# smartcar_shield.net
KiCad netlist of a schematic drawn in EAGLE
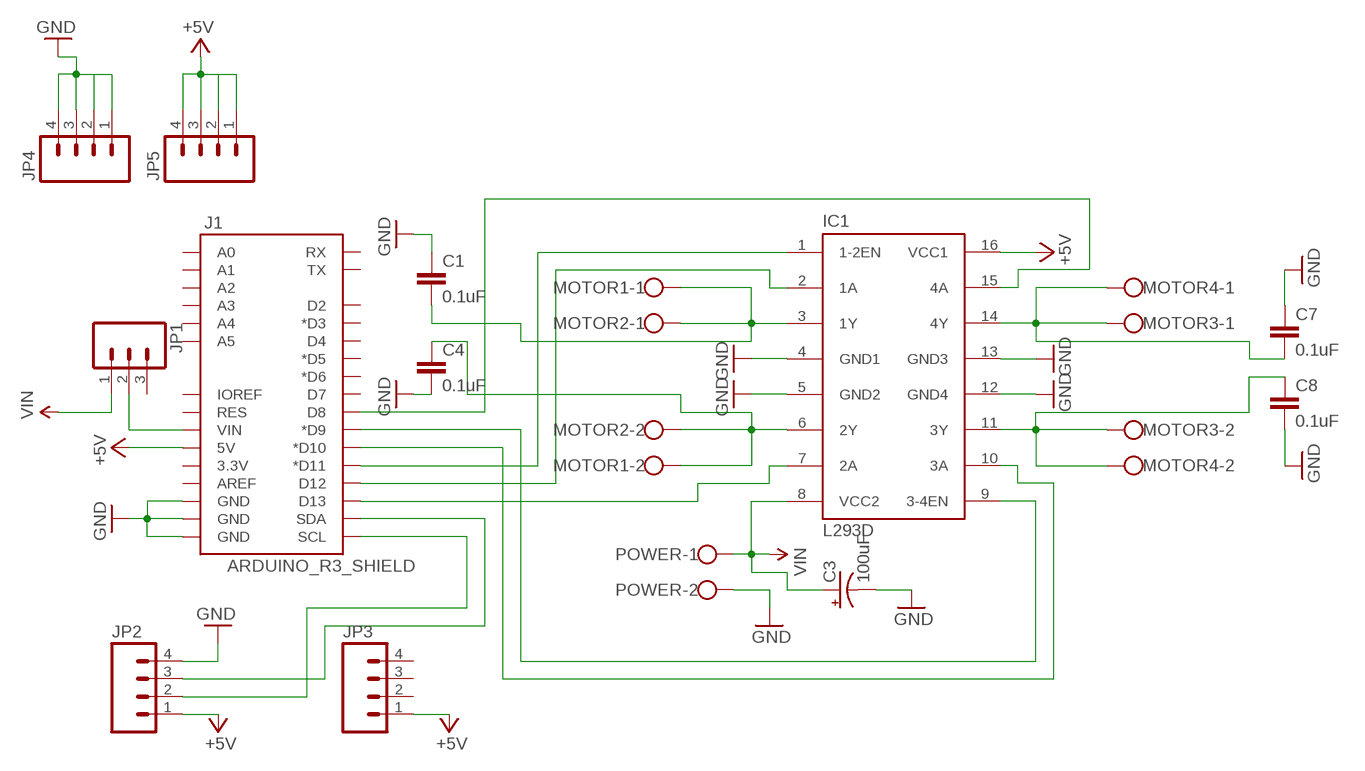
[diagram p0: schematic, sheet 1]

(export (version "E")
  (design (tool "Eeschema 10.0.6"))
  (components
    (comp (ref "C1")
      (value "0.1uF")
      (footprint "eagle-import:CAP-PTH-SMALL-KIT")
      (libsource (lib "eagle-import") (part "CAPKIT"))
    )
    (comp (ref "C3")
      (value "100uF")
      (footprint "eagle-import:CPOL-RADIAL-10UF-25V")
      (libsource (lib "eagle-import") (part "CAP_POLPTH2"))
    )
    (comp (ref "C4")
      (value "0.1uF")
      (footprint "eagle-import:CAP-PTH-SMALL-KIT")
      (libsource (lib "eagle-import") (part "CAPKIT"))
    )
    (comp (ref "C7")
      (value "0.1uF")
      (footprint "eagle-import:CAP-PTH-SMALL-KIT")
      (libsource (lib "eagle-import") (part "CAPKIT"))
    )
    (comp (ref "C8")
      (value "0.1uF")
      (footprint "eagle-import:CAP-PTH-SMALL-KIT")
      (libsource (lib "eagle-import") (part "CAPKIT"))
    )
    (comp (ref "IC1")
      (value "L293D")
      (footprint "eagle-import:DIL16")
      (libsource (lib "eagle-import") (part "L293D"))
    )
    (comp (ref "J1")
      (value "ARDUINO_R3_SHIELD")
      (footprint "eagle-import:UNO_R3_SHIELD")
      (libsource (lib "eagle-import") (part "ARDUINO_R3_SHIELD"))
    )
    (comp (ref "JP1")
      (value "M03PTH")
      (footprint "eagle-import:1X03")
      (libsource (lib "eagle-import") (part "M03PTH"))
    )
    (comp (ref "JP2")
      (value "M04NO_SILK_ALL_ROUND")
      (footprint "eagle-import:1X04_NO_SILK_ALL_ROUND")
      (libsource (lib "eagle-import") (part "M04NO_SILK_ALL_ROUND"))
    )
    (comp (ref "JP3")
      (value "M04NO_SILK_ALL_ROUND")
      (footprint "eagle-import:1X04_NO_SILK_ALL_ROUND")
      (libsource (lib "eagle-import") (part "M04NO_SILK_ALL_ROUND"))
    )
    (comp (ref "JP4")
      (value "M04NO_SILK_ALL_ROUND")
      (footprint "eagle-import:1X04_NO_SILK_ALL_ROUND")
      (libsource (lib "eagle-import") (part "M04NO_SILK_ALL_ROUND"))
    )
    (comp (ref "JP5")
      (value "M04NO_SILK_ALL_ROUND")
      (footprint "eagle-import:1X04_NO_SILK_ALL_ROUND")
      (libsource (lib "eagle-import") (part "M04NO_SILK_ALL_ROUND"))
    )
    (comp (ref "MOTOR1")
      (value "W237-102")
      (footprint "eagle-import:W237-102")
      (fields (field (name "MPN") "237-102"))
      (libsource (lib "eagle-import") (part "W237-102"))
    )
    (comp (ref "MOTOR2")
      (value "W237-102")
      (footprint "eagle-import:W237-102")
      (fields (field (name "MPN") "237-102"))
      (libsource (lib "eagle-import") (part "W237-102"))
    )
    (comp (ref "MOTOR3")
      (value "W237-102")
      (footprint "eagle-import:W237-102")
      (fields (field (name "MPN") "237-102"))
      (libsource (lib "eagle-import") (part "W237-102"))
    )
    (comp (ref "MOTOR4")
      (value "W237-102")
      (footprint "eagle-import:W237-102")
      (fields (field (name "MPN") "237-102"))
      (libsource (lib "eagle-import") (part "W237-102"))
    )
    (comp (ref "POWER")
      (value "W237-102")
      (footprint "eagle-import:W237-102")
      (fields (field (name "MPN") "237-102"))
      (libsource (lib "eagle-import") (part "W237-102"))
    )
  )
  (nets
    (net (code "1") (name "+5V") (class "Default")
      (node (ref "IC1") (pin "16") (pinfunction "VCC1_16") (pintype "power_in"))
      (node (ref "J1") (pin "5V") (pinfunction "5V_5V") (pintype "bidirectional"))
      (node (ref "JP2") (pin "1") (pinfunction "1_1") (pintype "passive"))
      (node (ref "JP3") (pin "1") (pinfunction "1_1") (pintype "passive"))
      (node (ref "JP5") (pin "1") (pinfunction "1_1") (pintype "passive"))
      (node (ref "JP5") (pin "2") (pinfunction "2_2") (pintype "passive"))
      (node (ref "JP5") (pin "3") (pinfunction "3_3") (pintype "passive"))
      (node (ref "JP5") (pin "4") (pinfunction "4_4") (pintype "passive"))
    )
    (net (code "2") (name "12V") (class "Default")
      (node (ref "C3") (pin "1") (pinfunction "+_1") (pintype "passive"))
      (node (ref "IC1") (pin "8") (pinfunction "VCC2_8") (pintype "power_in"))
      (node (ref "JP1") (pin "1") (pinfunction "1_1") (pintype "passive"))
      (node (ref "POWER") (pin "1") (pinfunction "KL_1") (pintype "passive"))
    )
    (net (code "3") (name "GND") (class "Default")
      (node (ref "C1") (pin "1") (pinfunction "1_1") (pintype "passive"))
      (node (ref "C3") (pin "2") (pinfunction "-_2") (pintype "passive"))
      (node (ref "C4") (pin "2") (pinfunction "2_2") (pintype "passive"))
      (node (ref "C7") (pin "1") (pinfunction "1_1") (pintype "passive"))
      (node (ref "C8") (pin "2") (pinfunction "2_2") (pintype "passive"))
      (node (ref "IC1") (pin "12") (pinfunction "GND4_12") (pintype "power_in"))
      (node (ref "IC1") (pin "13") (pinfunction "GND3_13") (pintype "power_in"))
      (node (ref "IC1") (pin "4") (pinfunction "GND1_4") (pintype "power_in"))
      (node (ref "IC1") (pin "5") (pinfunction "GND2_5") (pintype "power_in"))
      (node (ref "J1") (pin "GND@0") (pinfunction "GND_GND@0") (pintype "bidirectional"))
      (node (ref "J1") (pin "GND@1") (pinfunction "GND_GND@1") (pintype "bidirectional"))
      (node (ref "J1") (pin "GND@2") (pinfunction "GND_GND@2") (pintype "bidirectional"))
      (node (ref "JP2") (pin "4") (pinfunction "4_4") (pintype "passive"))
      (node (ref "JP4") (pin "1") (pinfunction "1_1") (pintype "passive"))
      (node (ref "JP4") (pin "2") (pinfunction "2_2") (pintype "passive"))
      (node (ref "JP4") (pin "3") (pinfunction "3_3") (pintype "passive"))
      (node (ref "JP4") (pin "4") (pinfunction "4_4") (pintype "passive"))
      (node (ref "POWER") (pin "2") (pinfunction "KL_2") (pintype "passive"))
    )
    (net (code "4") (name "Net-(IC1-1-2EN)") (class "Default")
      (node (ref "IC1") (pin "1") (pinfunction "1-2EN_1") (pintype "input"))
      (node (ref "J1") (pin "D11") (pinfunction "*D11_D11") (pintype "bidirectional"))
    )
    (net (code "5") (name "Net-(IC1-1A)") (class "Default")
      (node (ref "IC1") (pin "2") (pinfunction "1A_2") (pintype "input"))
      (node (ref "J1") (pin "D12") (pinfunction "D12_D12") (pintype "bidirectional"))
    )
    (net (code "6") (name "Net-(IC1-1Y)") (class "Default")
      (node (ref "C1") (pin "2") (pinfunction "2_2") (pintype "passive"))
      (node (ref "IC1") (pin "3") (pinfunction "1Y_3") (pintype "output"))
      (node (ref "MOTOR1") (pin "1") (pinfunction "KL_1") (pintype "passive"))
      (node (ref "MOTOR2") (pin "1") (pinfunction "KL_1") (pintype "passive"))
    )
    (net (code "7") (name "Net-(IC1-2A)") (class "Default")
      (node (ref "IC1") (pin "7") (pinfunction "2A_7") (pintype "input"))
      (node (ref "J1") (pin "D13") (pinfunction "D13_D13") (pintype "bidirectional"))
    )
    (net (code "8") (name "Net-(IC1-2Y)") (class "Default")
      (node (ref "C4") (pin "1") (pinfunction "1_1") (pintype "passive"))
      (node (ref "IC1") (pin "6") (pinfunction "2Y_6") (pintype "output"))
      (node (ref "MOTOR1") (pin "2") (pinfunction "KL_2") (pintype "passive"))
      (node (ref "MOTOR2") (pin "2") (pinfunction "KL_2") (pintype "passive"))
    )
    (net (code "9") (name "Net-(IC1-3-4EN)") (class "Default")
      (node (ref "IC1") (pin "9") (pinfunction "3-4EN_9") (pintype "input"))
      (node (ref "J1") (pin "D9") (pinfunction "*D9_D9") (pintype "bidirectional"))
    )
    (net (code "10") (name "Net-(IC1-3A)") (class "Default")
      (node (ref "IC1") (pin "10") (pinfunction "3A_10") (pintype "input"))
      (node (ref "J1") (pin "D10") (pinfunction "*D10_D10") (pintype "bidirectional"))
    )
    (net (code "11") (name "Net-(IC1-3Y)") (class "Default")
      (node (ref "C8") (pin "1") (pinfunction "1_1") (pintype "passive"))
      (node (ref "IC1") (pin "11") (pinfunction "3Y_11") (pintype "output"))
      (node (ref "MOTOR3") (pin "2") (pinfunction "KL_2") (pintype "passive"))
      (node (ref "MOTOR4") (pin "2") (pinfunction "KL_2") (pintype "passive"))
    )
    (net (code "12") (name "Net-(IC1-4A)") (class "Default")
      (node (ref "IC1") (pin "15") (pinfunction "4A_15") (pintype "input"))
      (node (ref "J1") (pin "D8") (pinfunction "D8_D8") (pintype "bidirectional"))
    )
    (net (code "13") (name "Net-(IC1-4Y)") (class "Default")
      (node (ref "C7") (pin "2") (pinfunction "2_2") (pintype "passive"))
      (node (ref "IC1") (pin "14") (pinfunction "4Y_14") (pintype "output"))
      (node (ref "MOTOR3") (pin "1") (pinfunction "KL_1") (pintype "passive"))
      (node (ref "MOTOR4") (pin "1") (pinfunction "KL_1") (pintype "passive"))
    )
    (net (code "14") (name "Net-(J1-PadSCL)") (class "Default")
      (node (ref "J1") (pin "SCL") (pinfunction "SCL_SCL") (pintype "bidirectional"))
      (node (ref "JP2") (pin "2") (pinfunction "2_2") (pintype "passive"))
    )
    (net (code "15") (name "Net-(J1-PadSDA)") (class "Default")
      (node (ref "J1") (pin "SDA") (pinfunction "SDA_SDA") (pintype "bidirectional"))
      (node (ref "JP2") (pin "3") (pinfunction "3_3") (pintype "passive"))
    )
    (net (code "16") (name "Net-(J1-PadVIN)") (class "Default")
      (node (ref "J1") (pin "VIN") (pinfunction "VIN_VIN") (pintype "bidirectional"))
      (node (ref "JP1") (pin "2") (pinfunction "2_2") (pintype "passive"))
    )
    (net (code "17") (name "unconnected-(J1-*D3-PadD3)") (class "Default")
      (node (ref "J1") (pin "D3") (pinfunction "*D3_D3") (pintype "bidirectional"))
    )
    (net (code "18") (name "unconnected-(J1-*D5-PadD5)") (class "Default")
      (node (ref "J1") (pin "D5") (pinfunction "*D5_D5") (pintype "bidirectional"))
    )
    (net (code "19") (name "unconnected-(J1-*D6-PadD6)") (class "Default")
      (node (ref "J1") (pin "D6") (pinfunction "*D6_D6") (pintype "bidirectional"))
    )
    (net (code "20") (name "unconnected-(J1-Pad3.3V)") (class "Default")
      (node (ref "J1") (pin "3.3V") (pinfunction "3.3V_3.3V") (pintype "bidirectional"))
    )
    (net (code "21") (name "unconnected-(J1-PadA0)") (class "Default")
      (node (ref "J1") (pin "A0") (pinfunction "A0_A0") (pintype "bidirectional"))
    )
    (net (code "22") (name "unconnected-(J1-PadA1)") (class "Default")
      (node (ref "J1") (pin "A1") (pinfunction "A1_A1") (pintype "bidirectional"))
    )
    (net (code "23") (name "unconnected-(J1-PadA2)") (class "Default")
      (node (ref "J1") (pin "A2") (pinfunction "A2_A2") (pintype "bidirectional"))
    )
    (net (code "24") (name "unconnected-(J1-PadA3)") (class "Default")
      (node (ref "J1") (pin "A3") (pinfunction "A3_A3") (pintype "bidirectional"))
    )
    (net (code "25") (name "unconnected-(J1-PadA4)") (class "Default")
      (node (ref "J1") (pin "A4") (pinfunction "A4_A4") (pintype "bidirectional"))
    )
    (net (code "26") (name "unconnected-(J1-PadA5)") (class "Default")
      (node (ref "J1") (pin "A5") (pinfunction "A5_A5") (pintype "bidirectional"))
    )
    (net (code "27") (name "unconnected-(J1-PadAREF)") (class "Default")
      (node (ref "J1") (pin "AREF") (pinfunction "AREF_AREF") (pintype "bidirectional"))
    )
    (net (code "28") (name "unconnected-(J1-PadD2)") (class "Default")
      (node (ref "J1") (pin "D2") (pinfunction "D2_D2") (pintype "bidirectional"))
    )
    (net (code "29") (name "unconnected-(J1-PadD4)") (class "Default")
      (node (ref "J1") (pin "D4") (pinfunction "D4_D4") (pintype "bidirectional"))
    )
    (net (code "30") (name "unconnected-(J1-PadD7)") (class "Default")
      (node (ref "J1") (pin "D7") (pinfunction "D7_D7") (pintype "bidirectional"))
    )
    (net (code "31") (name "unconnected-(J1-PadIOREF)") (class "Default")
      (node (ref "J1") (pin "IOREF") (pinfunction "IOREF_IOREF") (pintype "bidirectional"))
    )
    (net (code "32") (name "unconnected-(J1-PadRES)") (class "Default")
      (node (ref "J1") (pin "RES") (pinfunction "RES_RES") (pintype "bidirectional"))
    )
    (net (code "33") (name "unconnected-(J1-PadRX)") (class "Default")
      (node (ref "J1") (pin "RX") (pinfunction "RX_RX") (pintype "bidirectional"))
    )
    (net (code "34") (name "unconnected-(J1-PadTX)") (class "Default")
      (node (ref "J1") (pin "TX") (pinfunction "TX_TX") (pintype "bidirectional"))
    )
    (net (code "35") (name "unconnected-(JP1-Pad3)") (class "Default")
      (node (ref "JP1") (pin "3") (pinfunction "3_3") (pintype "passive"))
    )
    (net (code "36") (name "unconnected-(JP3-Pad2)") (class "Default")
      (node (ref "JP3") (pin "2") (pinfunction "2_2") (pintype "passive"))
    )
    (net (code "37") (name "unconnected-(JP3-Pad3)") (class "Default")
      (node (ref "JP3") (pin "3") (pinfunction "3_3") (pintype "passive"))
    )
    (net (code "38") (name "unconnected-(JP3-Pad4)") (class "Default")
      (node (ref "JP3") (pin "4") (pinfunction "4_4") (pintype "passive"))
    )
  )
)
